# Main.net
KiCad netlist of a schematic drawn in Altium Designer
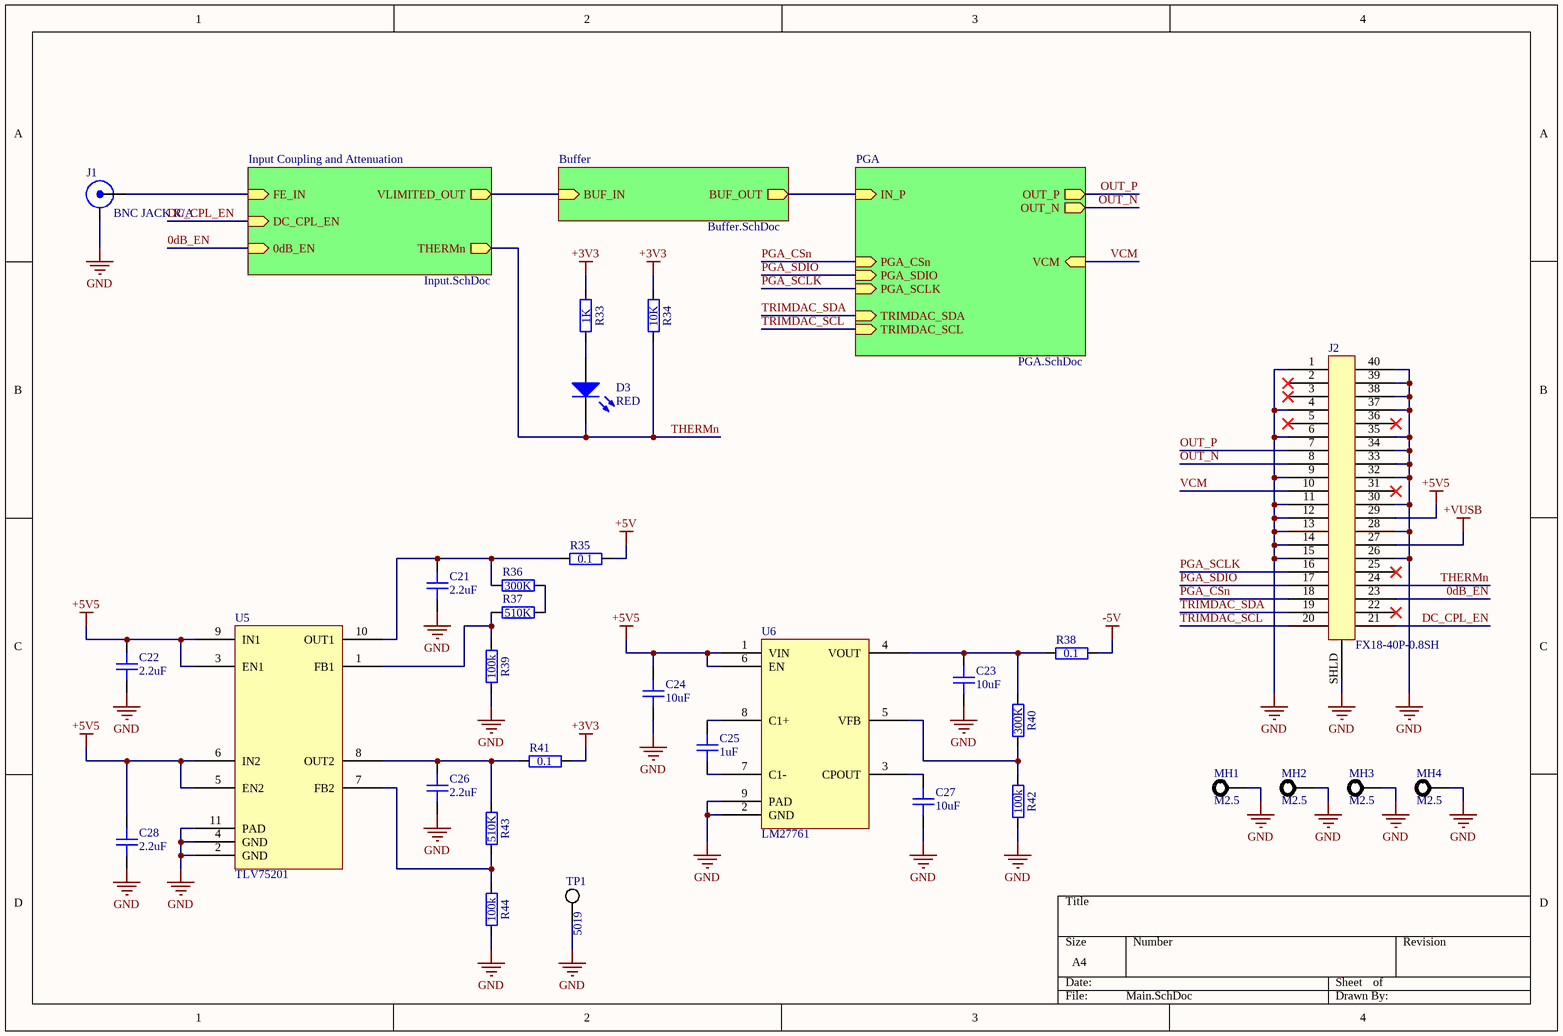
[diagram p0: Main.SchDoc]

(export (version "E")
  (design (tool "Eeschema 10.0.6"))
  (components
    (comp (ref "C21")
      (value "2.2uF")
      (footprint "GEN_C_0402")
      (fields (field (name "Comment") "CAP 2.2uF 10V X5R 0402"))
      (libsource (lib "DSO") (part "CAP 2.2uF 10V X5R 0402"))
    )
    (comp (ref "C22")
      (value "2.2uF")
      (footprint "GEN_C_0402")
      (fields (field (name "Comment") "CAP 2.2uF 10V X5R 0402"))
      (libsource (lib "DSO") (part "CAP 2.2uF 10V X5R 0402"))
    )
    (comp (ref "C23")
      (value "10uF")
      (footprint "GEN_C_0603")
      (fields (field (name "Comment") "CAP 10uF 10V X5R 0603"))
      (libsource (lib "DSO") (part "CAP 10uF 10V X5R 0603"))
    )
    (comp (ref "C24")
      (value "10uF")
      (footprint "GEN_C_0603")
      (fields (field (name "Comment") "CAP 10uF 10V X5R 0603"))
      (libsource (lib "DSO") (part "CAP 10uF 10V X5R 0603"))
    )
    (comp (ref "C25")
      (value "1uF")
      (footprint "GEN_C_0402")
      (fields (field (name "Comment") "CAP 1uF 25V X5R 0402"))
      (libsource (lib "DSO") (part "CAP 1uF 25V X5R 0402"))
    )
    (comp (ref "C26")
      (value "2.2uF")
      (footprint "GEN_C_0402")
      (fields (field (name "Comment") "CAP 2.2uF 10V X5R 0402"))
      (libsource (lib "DSO") (part "CAP 2.2uF 10V X5R 0402"))
    )
    (comp (ref "C27")
      (value "10uF")
      (footprint "GEN_C_0603")
      (fields (field (name "Comment") "CAP 10uF 10V X5R 0603"))
      (libsource (lib "DSO") (part "CAP 10uF 10V X5R 0603"))
    )
    (comp (ref "C28")
      (value "2.2uF")
      (footprint "GEN_C_0402")
      (fields (field (name "Comment") "CAP 2.2uF 10V X5R 0402"))
      (libsource (lib "DSO") (part "CAP 2.2uF 10V X5R 0402"))
    )
    (comp (ref "D3")
      (value "RED")
      (footprint "LED_0603_APT1608")
      (libsource (lib "DSO") (part "LED RED 0603 APT1608"))
    )
    (comp (ref "J1")
      (value "BNC JACK R/A")
      (footprint "MOL_0731000105")
      (libsource (lib "DSO") (part "BNC JACK R/A"))
    )
    (comp (ref "J2")
      (value "FX18-40P-0.8SH")
      (footprint "HIR_FX18-40P-0.8SH")
      (libsource (lib "DSO") (part "CONN HDR FX18-40P-0.8SH"))
    )
    (comp (ref "MH1") (value "M2.5") (footprint "MH M2.5") (libsource (lib "DSO") (part "MH M2.5")))
    (comp (ref "MH2") (value "M2.5") (footprint "MH M2.5") (libsource (lib "DSO") (part "MH M2.5")))
    (comp (ref "MH3") (value "M2.5") (footprint "MH M2.5") (libsource (lib "DSO") (part "MH M2.5")))
    (comp (ref "MH4") (value "M2.5") (footprint "MH M2.5") (libsource (lib "DSO") (part "MH M2.5")))
    (comp (ref "R33")
      (value "1K")
      (footprint "GEN_R_0402")
      (fields (field (name "TOLERANCE") "1%") (field (name "Comment") "RES 1K OHM 1% 1/10W 0402"))
      (libsource (lib "DSO") (part "RES 1K OHM 1% 1/10W 0402"))
    )
    (comp (ref "R34")
      (value "10K")
      (footprint "GEN_R_0402")
      (fields (field (name "TOLERANCE") "1%") (field (name "Comment") "RES 10K OHM 1% 1/10W 0402"))
      (libsource (lib "DSO") (part "RES 10K OHM 1% 1/10W 0402"))
    )
    (comp (ref "R35")
      (value "0.1")
      (footprint "GEN_R_0402")
      (fields (field (name "TOLERANCE") "1%"))
      (libsource (lib "DSO") (part "RES 0.1 OHM 1% 1/6W 0402"))
    )
    (comp (ref "R36")
      (value "300K")
      (footprint "GEN_R_0402")
      (fields (field (name "TOLERANCE") "1%") (field (name "Comment") "RES 300K OHM 1% 1/10W 0402"))
      (libsource (lib "") (part "RES 300K OHM 1% 1/10W 0402_1"))
    )
    (comp (ref "R37")
      (value "510K")
      (footprint "GEN_R_0402")
      (fields (field (name "TOLERANCE") "1%") (field (name "Comment") "RES 510K OHM 1% 1/10W 0402"))
      (libsource (lib "DSO") (part "RES 510K OHM 1% 1/10W 0402"))
    )
    (comp (ref "R38")
      (value "0.1")
      (footprint "GEN_R_0402")
      (fields (field (name "TOLERANCE") "1%"))
      (libsource (lib "DSO") (part "RES 0.1 OHM 1% 1/6W 0402"))
    )
    (comp (ref "R39")
      (value "100k")
      (footprint "GEN_R_0402")
      (fields (field (name "TOLERANCE") "1%") (field (name "Comment") "RES 100K OHM 1% 1/10W 0402"))
      (libsource (lib "DSO") (part "RES 100K OHM 1% 1/10W 0402"))
    )
    (comp (ref "R40")
      (value "300K")
      (footprint "GEN_R_0402")
      (fields (field (name "TOLERANCE") "1%") (field (name "Comment") "RES 300K OHM 1% 1/10W 0402"))
      (libsource (lib "DSO") (part "RES 300K OHM 1% 1/10W 0402"))
    )
    (comp (ref "R41")
      (value "0.1")
      (footprint "GEN_R_0402")
      (fields (field (name "TOLERANCE") "1%"))
      (libsource (lib "DSO") (part "RES 0.1 OHM 1% 1/6W 0402"))
    )
    (comp (ref "R42")
      (value "100k")
      (footprint "GEN_R_0402")
      (fields (field (name "TOLERANCE") "1%") (field (name "Comment") "RES 100K OHM 1% 1/10W 0402"))
      (libsource (lib "DSO") (part "RES 100K OHM 1% 1/10W 0402"))
    )
    (comp (ref "R43")
      (value "510K")
      (footprint "GEN_R_0402")
      (fields (field (name "TOLERANCE") "1%") (field (name "Comment") "RES 510K OHM 1% 1/10W 0402"))
      (libsource (lib "") (part "RES 510K OHM 1% 1/10W 0402_1"))
    )
    (comp (ref "R44")
      (value "100k")
      (footprint "GEN_R_0402")
      (fields (field (name "TOLERANCE") "1%") (field (name "Comment") "RES 100K OHM 1% 1/10W 0402"))
      (libsource (lib "DSO") (part "RES 100K OHM 1% 1/10W 0402"))
    )
    (comp (ref "TP1") (value "5019") (footprint "KEY_5019") (libsource (lib "DSO") (part "TP KEYSTONE 5019")))
    (comp (ref "U5")
      (value "TLV75201")
      (footprint "TI_WSON10_DSQ0010A")
      (libsource (lib "DSO") (part "IC LDO TLV75201"))
    )
    (comp (ref "U6")
      (value "LM27761")
      (footprint "TI_WSON8_DSG0008A")
      (libsource (lib "DSO") (part "IC CPUMP LM27761"))
    )
  )
  (nets
    (net (code "1") (name "+3V3") (class "Default")
      (node (ref "R33") (pin "1") (pinfunction "1_1") (pintype "passive"))
      (node (ref "R34") (pin "2") (pinfunction "2_2") (pintype "passive"))
      (node (ref "R41") (pin "2") (pinfunction "2_2") (pintype "passive"))
    )
    (net (code "2") (name "+5V") (class "Default")
      (node (ref "R35") (pin "2") (pinfunction "2_2") (pintype "passive"))
    )
    (net (code "3") (name "+5V5") (class "Default")
      (node (ref "C22") (pin "2") (pinfunction "2_2") (pintype "passive"))
      (node (ref "C24") (pin "2") (pinfunction "2_2") (pintype "passive"))
      (node (ref "C28") (pin "2") (pinfunction "2_2") (pintype "passive"))
      (node (ref "J2") (pin "29") (pinfunction "29_29") (pintype "passive"))
      (node (ref "U5") (pin "3") (pinfunction "EN1_3") (pintype "passive"))
      (node (ref "U5") (pin "5") (pinfunction "EN2_5") (pintype "passive"))
      (node (ref "U5") (pin "6") (pinfunction "IN2_6") (pintype "power_in"))
      (node (ref "U5") (pin "9") (pinfunction "IN1_9") (pintype "power_in"))
      (node (ref "U6") (pin "1") (pinfunction "VIN_1") (pintype "power_in"))
      (node (ref "U6") (pin "6") (pinfunction "EN_6") (pintype "passive"))
    )
    (net (code "4") (name "+VUSB") (class "Default")
      (node (ref "J2") (pin "27") (pinfunction "27_27") (pintype "passive"))
    )
    (net (code "5") (name "-5V") (class "Default")
      (node (ref "R38") (pin "2") (pinfunction "2_2") (pintype "passive"))
    )
    (net (code "6") (name "/0dB_EN") (class "Default")
      (node (ref "J2") (pin "23") (pinfunction "23_23") (pintype "passive"))
    )
    (net (code "8") (name "/DC_CPL_EN") (class "Default")
      (node (ref "J2") (pin "21") (pinfunction "21_21") (pintype "passive"))
    )
    (net (code "9") (name "/FE_IN") (class "Default")
      (node (ref "J1") (pin "1") (pinfunction "Signal_1") (pintype "passive"))
    )
    (net (code "10") (name "/OUT_N") (class "Default")
      (node (ref "J2") (pin "8") (pinfunction "8_8") (pintype "passive"))
    )
    (net (code "11") (name "/OUT_P") (class "Default")
      (node (ref "J2") (pin "7") (pinfunction "7_7") (pintype "passive"))
    )
    (net (code "12") (name "/PGA_CSn") (class "Default")
      (node (ref "J2") (pin "18") (pinfunction "18_18") (pintype "passive"))
    )
    (net (code "13") (name "/PGA_SCLK") (class "Default")
      (node (ref "J2") (pin "16") (pinfunction "16_16") (pintype "passive"))
    )
    (net (code "14") (name "/PGA_SDIO") (class "Default")
      (node (ref "J2") (pin "17") (pinfunction "17_17") (pintype "passive"))
    )
    (net (code "15") (name "/THERMn") (class "Default")
      (node (ref "D3") (pin "1") (pinfunction "K_1") (pintype "passive"))
      (node (ref "J2") (pin "24") (pinfunction "24_24") (pintype "passive"))
      (node (ref "R34") (pin "1") (pinfunction "1_1") (pintype "passive"))
    )
    (net (code "16") (name "/TRIMDAC_SCL") (class "Default")
      (node (ref "J2") (pin "20") (pinfunction "20_20") (pintype "passive"))
    )
    (net (code "17") (name "/TRIMDAC_SDA") (class "Default")
      (node (ref "J2") (pin "19") (pinfunction "19_19") (pintype "passive"))
    )
    (net (code "18") (name "/VCM") (class "Default")
      (node (ref "J2") (pin "10") (pinfunction "10_10") (pintype "passive"))
    )
    (net (code "20") (name "GND") (class "Default")
      (node (ref "C21") (pin "1") (pinfunction "1_1") (pintype "passive"))
      (node (ref "C22") (pin "1") (pinfunction "1_1") (pintype "passive"))
      (node (ref "C23") (pin "1") (pinfunction "1_1") (pintype "passive"))
      (node (ref "C24") (pin "1") (pinfunction "1_1") (pintype "passive"))
      (node (ref "C26") (pin "1") (pinfunction "1_1") (pintype "passive"))
      (node (ref "C27") (pin "1") (pinfunction "1_1") (pintype "passive"))
      (node (ref "C28") (pin "1") (pinfunction "1_1") (pintype "passive"))
      (node (ref "J1") (pin "2") (pinfunction "SHIELD_2") (pintype "passive"))
      (node (ref "J2") (pin "1") (pinfunction "1_1") (pintype "passive"))
      (node (ref "J2") (pin "11") (pinfunction "11_11") (pintype "passive"))
      (node (ref "J2") (pin "12") (pinfunction "12_12") (pintype "passive"))
      (node (ref "J2") (pin "13") (pinfunction "13_13") (pintype "passive"))
      (node (ref "J2") (pin "14") (pinfunction "14_14") (pintype "passive"))
      (node (ref "J2") (pin "15") (pinfunction "15_15") (pintype "passive"))
      (node (ref "J2") (pin "26") (pinfunction "26_26") (pintype "passive"))
      (node (ref "J2") (pin "28") (pinfunction "28_28") (pintype "passive"))
      (node (ref "J2") (pin "30") (pinfunction "30_30") (pintype "passive"))
      (node (ref "J2") (pin "32") (pinfunction "32_32") (pintype "passive"))
      (node (ref "J2") (pin "33") (pinfunction "33_33") (pintype "passive"))
      (node (ref "J2") (pin "34") (pinfunction "34_34") (pintype "passive"))
      (node (ref "J2") (pin "35") (pinfunction "35_35") (pintype "passive"))
      (node (ref "J2") (pin "37") (pinfunction "37_37") (pintype "passive"))
      (node (ref "J2") (pin "38") (pinfunction "38_38") (pintype "passive"))
      (node (ref "J2") (pin "39") (pinfunction "39_39") (pintype "passive"))
      (node (ref "J2") (pin "4") (pinfunction "4_4") (pintype "passive"))
      (node (ref "J2") (pin "40") (pinfunction "40_40") (pintype "passive"))
      (node (ref "J2") (pin "6") (pinfunction "6_6") (pintype "passive"))
      (node (ref "J2") (pin "9") (pinfunction "9_9") (pintype "passive"))
      (node (ref "J2") (pin "SHLD") (pinfunction "SHLD_SHLD") (pintype "passive"))
      (node (ref "MH1") (pin "1") (pinfunction "1_1") (pintype "passive"))
      (node (ref "MH2") (pin "1") (pinfunction "1_1") (pintype "passive"))
      (node (ref "MH3") (pin "1") (pinfunction "1_1") (pintype "passive"))
      (node (ref "MH4") (pin "1") (pinfunction "1_1") (pintype "passive"))
      (node (ref "R39") (pin "1") (pinfunction "1_1") (pintype "passive"))
      (node (ref "R42") (pin "1") (pinfunction "1_1") (pintype "passive"))
      (node (ref "R44") (pin "1") (pinfunction "1_1") (pintype "passive"))
      (node (ref "TP1") (pin "1") (pinfunction "1_1") (pintype "passive"))
      (node (ref "U5") (pin "11") (pinfunction "PAD_11") (pintype "power_in"))
      (node (ref "U5") (pin "2") (pinfunction "GND_2") (pintype "power_in"))
      (node (ref "U5") (pin "4") (pinfunction "GND_4") (pintype "power_in"))
      (node (ref "U6") (pin "2") (pinfunction "GND_2") (pintype "power_in"))
      (node (ref "U6") (pin "9") (pinfunction "PAD_9") (pintype "power_in"))
    )
    (net (code "21") (name "Net-(D3-A)") (class "Default")
      (node (ref "D3") (pin "2") (pinfunction "A_2") (pintype "passive"))
      (node (ref "R33") (pin "2") (pinfunction "2_2") (pintype "passive"))
    )
    (net (code "22") (name "Net-(R36-Pad1)") (class "Default")
      (node (ref "R36") (pin "1") (pinfunction "1_1") (pintype "passive"))
      (node (ref "R37") (pin "1") (pinfunction "1_1") (pintype "passive"))
    )
    (net (code "23") (name "Net-(U5-FB1)") (class "Default")
      (node (ref "R37") (pin "2") (pinfunction "2_2") (pintype "passive"))
      (node (ref "R39") (pin "2") (pinfunction "2_2") (pintype "passive"))
      (node (ref "U5") (pin "1") (pinfunction "FB1_1") (pintype "passive"))
    )
    (net (code "24") (name "Net-(U5-FB2)") (class "Default")
      (node (ref "R43") (pin "1") (pinfunction "1_1") (pintype "passive"))
      (node (ref "R44") (pin "2") (pinfunction "2_2") (pintype "passive"))
      (node (ref "U5") (pin "7") (pinfunction "FB2_7") (pintype "passive"))
    )
    (net (code "25") (name "Net-(U5-OUT1)") (class "Default")
      (node (ref "C21") (pin "2") (pinfunction "2_2") (pintype "passive"))
      (node (ref "R35") (pin "1") (pinfunction "1_1") (pintype "passive"))
      (node (ref "R36") (pin "2") (pinfunction "2_2") (pintype "passive"))
      (node (ref "U5") (pin "10") (pinfunction "OUT1_10") (pintype "power_in"))
    )
    (net (code "26") (name "Net-(U5-OUT2)") (class "Default")
      (node (ref "C26") (pin "2") (pinfunction "2_2") (pintype "passive"))
      (node (ref "R41") (pin "1") (pinfunction "1_1") (pintype "passive"))
      (node (ref "R43") (pin "2") (pinfunction "2_2") (pintype "passive"))
      (node (ref "U5") (pin "8") (pinfunction "OUT2_8") (pintype "power_in"))
    )
    (net (code "27") (name "Net-(U6-C1+)") (class "Default")
      (node (ref "C25") (pin "2") (pinfunction "2_2") (pintype "passive"))
      (node (ref "U6") (pin "8") (pinfunction "C1+_8") (pintype "passive"))
    )
    (net (code "28") (name "Net-(U6-C1-)") (class "Default")
      (node (ref "C25") (pin "1") (pinfunction "1_1") (pintype "passive"))
      (node (ref "U6") (pin "7") (pinfunction "C1-_7") (pintype "passive"))
    )
    (net (code "29") (name "Net-(U6-CPOUT)") (class "Default")
      (node (ref "C27") (pin "2") (pinfunction "2_2") (pintype "passive"))
      (node (ref "U6") (pin "3") (pinfunction "CPOUT_3") (pintype "passive"))
    )
    (net (code "30") (name "Net-(U6-VFB)") (class "Default")
      (node (ref "R40") (pin "1") (pinfunction "1_1") (pintype "passive"))
      (node (ref "R42") (pin "2") (pinfunction "2_2") (pintype "passive"))
      (node (ref "U6") (pin "5") (pinfunction "VFB_5") (pintype "passive"))
    )
    (net (code "31") (name "Net-(U6-VOUT)") (class "Default")
      (node (ref "C23") (pin "2") (pinfunction "2_2") (pintype "passive"))
      (node (ref "R38") (pin "1") (pinfunction "1_1") (pintype "passive"))
      (node (ref "R40") (pin "2") (pinfunction "2_2") (pintype "passive"))
      (node (ref "U6") (pin "4") (pinfunction "VOUT_4") (pintype "power_in"))
    )
    (net (code "32") (name "unconnected-(J2-Pad2)") (class "Default")
      (node (ref "J2") (pin "2") (pinfunction "2_2") (pintype "passive+no_connect"))
    )
    (net (code "33") (name "unconnected-(J2-Pad3)") (class "Default")
      (node (ref "J2") (pin "3") (pinfunction "3_3") (pintype "passive+no_connect"))
    )
    (net (code "34") (name "unconnected-(J2-Pad5)") (class "Default")
      (node (ref "J2") (pin "5") (pinfunction "5_5") (pintype "passive+no_connect"))
    )
    (net (code "35") (name "unconnected-(J2-Pad22)") (class "Default")
      (node (ref "J2") (pin "22") (pinfunction "22_22") (pintype "passive+no_connect"))
    )
    (net (code "36") (name "unconnected-(J2-Pad25)") (class "Default")
      (node (ref "J2") (pin "25") (pinfunction "25_25") (pintype "passive+no_connect"))
    )
    (net (code "37") (name "unconnected-(J2-Pad31)") (class "Default")
      (node (ref "J2") (pin "31") (pinfunction "31_31") (pintype "passive+no_connect"))
    )
    (net (code "38") (name "unconnected-(J2-Pad36)") (class "Default")
      (node (ref "J2") (pin "36") (pinfunction "36_36") (pintype "passive+no_connect"))
    )
  )
)
